# TesteRJ45.net
KiCad netlist of a schematic drawn in Altium Designer
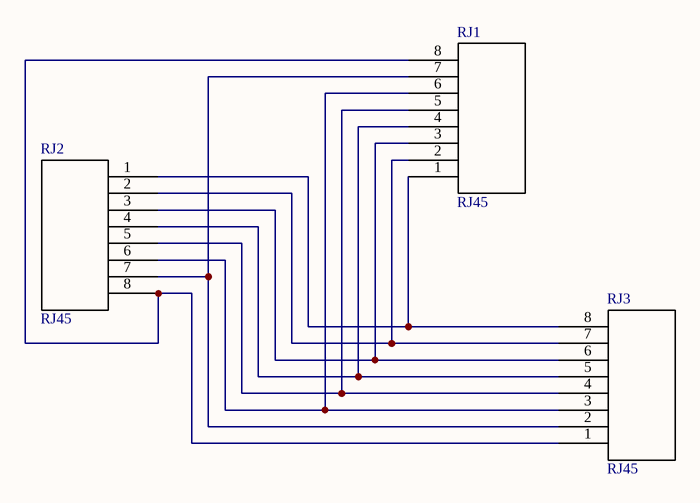
[diagram p0: TesteRJ45.SchDoc]

(export (version "E")
  (design (tool "Eeschema 10.0.6"))
  (components
    (comp (ref "RJ1")
      (value "RJ45")
      (footprint "RJ45_Simples")
      (libsource (lib "Componentes_Open") (part "RJ45"))
    )
    (comp (ref "RJ2")
      (value "RJ45")
      (footprint "RJ45_Simples")
      (libsource (lib "Componentes_Open") (part "RJ45"))
    )
    (comp (ref "RJ3")
      (value "RJ45")
      (footprint "RJ45_Simples")
      (libsource (lib "Componentes_Open") (part "RJ45"))
    )
  )
  (nets
    (net (code "1") (name "Net-(RJ1-9)") (class "Default")
      (node (ref "RJ1") (pin "1") (pinfunction "9_1") (pintype "passive"))
      (node (ref "RJ2") (pin "1") (pinfunction "9_1") (pintype "passive"))
      (node (ref "RJ3") (pin "8") (pinfunction "8_8") (pintype "passive"))
    )
    (net (code "2") (name "Net-(RJ1-Pad2)") (class "Default")
      (node (ref "RJ1") (pin "2") (pinfunction "2_2") (pintype "passive"))
      (node (ref "RJ2") (pin "2") (pinfunction "2_2") (pintype "passive"))
      (node (ref "RJ3") (pin "7") (pinfunction "7_7") (pintype "passive"))
    )
    (net (code "3") (name "Net-(RJ1-Pad3)") (class "Default")
      (node (ref "RJ1") (pin "3") (pinfunction "3_3") (pintype "passive"))
      (node (ref "RJ2") (pin "3") (pinfunction "3_3") (pintype "passive"))
      (node (ref "RJ3") (pin "6") (pinfunction "6_6") (pintype "passive"))
    )
    (net (code "4") (name "Net-(RJ1-Pad4)") (class "Default")
      (node (ref "RJ1") (pin "4") (pinfunction "4_4") (pintype "passive"))
      (node (ref "RJ2") (pin "4") (pinfunction "4_4") (pintype "passive"))
      (node (ref "RJ3") (pin "5") (pinfunction "5_5") (pintype "passive"))
    )
    (net (code "5") (name "Net-(RJ1-Pad5)") (class "Default")
      (node (ref "RJ1") (pin "5") (pinfunction "5_5") (pintype "passive"))
      (node (ref "RJ2") (pin "5") (pinfunction "5_5") (pintype "passive"))
      (node (ref "RJ3") (pin "4") (pinfunction "4_4") (pintype "passive"))
    )
    (net (code "6") (name "Net-(RJ1-Pad6)") (class "Default")
      (node (ref "RJ1") (pin "6") (pinfunction "6_6") (pintype "passive"))
      (node (ref "RJ2") (pin "6") (pinfunction "6_6") (pintype "passive"))
      (node (ref "RJ3") (pin "3") (pinfunction "3_3") (pintype "passive"))
    )
    (net (code "7") (name "Net-(RJ1-Pad7)") (class "Default")
      (node (ref "RJ1") (pin "7") (pinfunction "7_7") (pintype "passive"))
      (node (ref "RJ2") (pin "7") (pinfunction "7_7") (pintype "passive"))
      (node (ref "RJ3") (pin "2") (pinfunction "2_2") (pintype "passive"))
    )
    (net (code "8") (name "Net-(RJ3-9)") (class "Default")
      (node (ref "RJ1") (pin "8") (pinfunction "8_8") (pintype "passive"))
      (node (ref "RJ2") (pin "8") (pinfunction "8_8") (pintype "passive"))
      (node (ref "RJ3") (pin "1") (pinfunction "9_1") (pintype "passive"))
    )
  )
)
